# Button.net
KiCad netlist of a schematic drawn in EAGLE
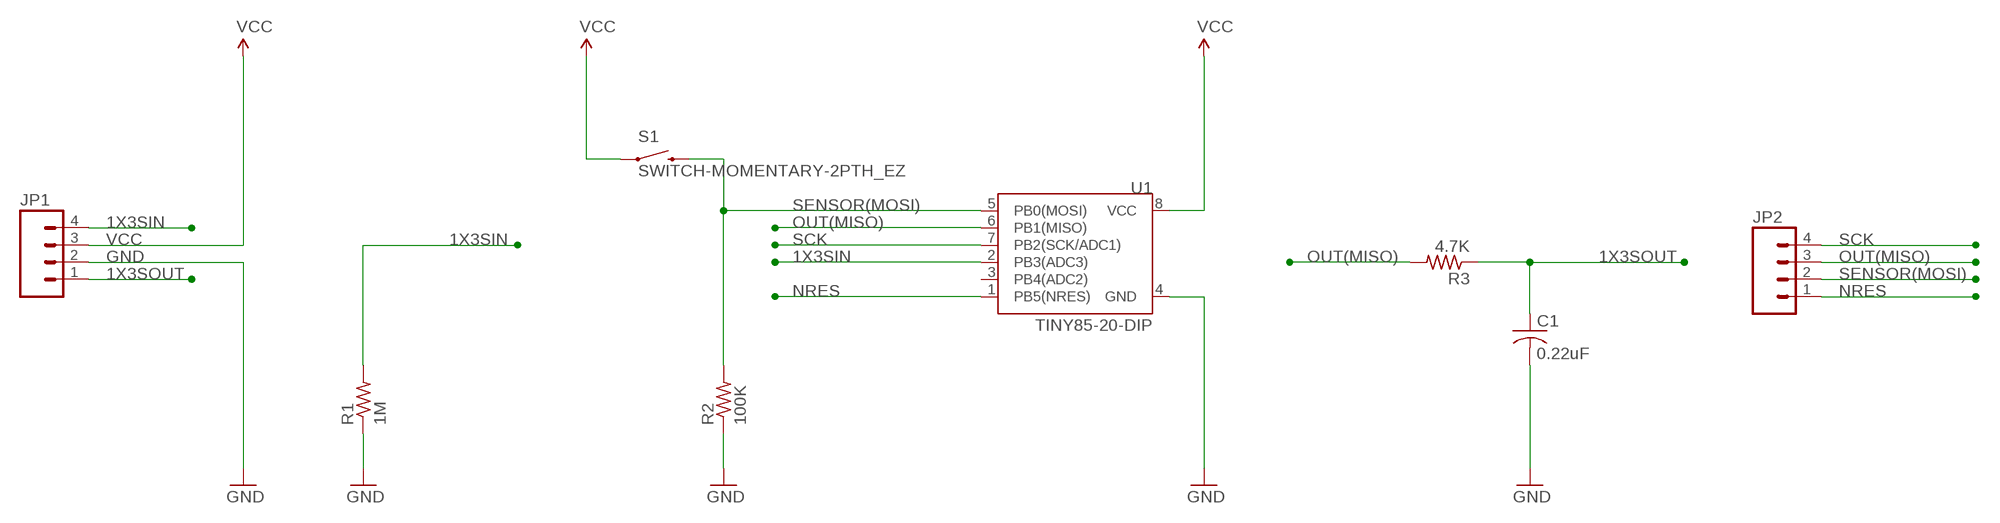
[diagram p0: schematic, sheet 1]

(export (version "E")
  (design (tool "Eeschema 10.0.6"))
  (components
    (comp (ref "C1")
      (value "0.22uF")
      (footprint "eagle-import:C0402")
      (libsource (lib "eagle-import") (part "C-USC0402"))
    )
    (comp (ref "JP1")
      (value "M04PTH")
      (footprint "eagle-import:1X04")
      (libsource (lib "eagle-import") (part "M04PTH"))
    )
    (comp (ref "JP2")
      (value "M04PTH")
      (footprint "eagle-import:1X04")
      (libsource (lib "eagle-import") (part "M04PTH"))
    )
    (comp (ref "R1")
      (value "1M")
      (footprint "eagle-import:R0603")
      (libsource (lib "eagle-import") (part "R-US_R0603"))
    )
    (comp (ref "R2")
      (value "100K")
      (footprint "eagle-import:R0603")
      (libsource (lib "eagle-import") (part "R-US_R0603"))
    )
    (comp (ref "R3")
      (value "4.7K")
      (footprint "eagle-import:R0603")
      (libsource (lib "eagle-import") (part "R-US_R0603"))
    )
    (comp (ref "S1")
      (value "SWITCH-MOMENTARY-2PTH_EZ")
      (footprint "eagle-import:TACTILE-PTH-EZ")
      (libsource (lib "eagle-import") (part "SWITCH-MOMENTARY-2PTH_EZ"))
    )
    (comp (ref "U1")
      (value "TINY85-20-DIP")
      (footprint "eagle-import:DIP08")
      (libsource (lib "eagle-import") (part "ATTINY45TINY85-20-DIP"))
    )
  )
  (nets
    (net (code "1") (name "/1X3SIN") (class "Default")
      (node (ref "JP1") (pin "4") (pinfunction "4_4") (pintype "passive"))
      (node (ref "R1") (pin "2") (pinfunction "2_2") (pintype "passive"))
      (node (ref "U1") (pin "2") (pinfunction "PB3(ADC3)_2") (pintype "bidirectional"))
    )
    (net (code "2") (name "/1X3SOUT") (class "Default")
      (node (ref "C1") (pin "1") (pinfunction "1_1") (pintype "passive"))
      (node (ref "JP1") (pin "1") (pinfunction "1_1") (pintype "passive"))
      (node (ref "R3") (pin "1") (pinfunction "1_1") (pintype "passive"))
    )
    (net (code "3") (name "/NRES") (class "Default")
      (node (ref "JP2") (pin "1") (pinfunction "1_1") (pintype "passive"))
      (node (ref "U1") (pin "1") (pinfunction "PB5(NRES)_1") (pintype "bidirectional"))
    )
    (net (code "4") (name "/OUT(MISO)") (class "Default")
      (node (ref "JP2") (pin "3") (pinfunction "3_3") (pintype "passive"))
      (node (ref "R3") (pin "2") (pinfunction "2_2") (pintype "passive"))
      (node (ref "U1") (pin "6") (pinfunction "PB1(MISO)_6") (pintype "bidirectional"))
    )
    (net (code "5") (name "/SCK") (class "Default")
      (node (ref "JP2") (pin "4") (pinfunction "4_4") (pintype "passive"))
      (node (ref "U1") (pin "7") (pinfunction "PB2(SCK/ADC1)_7") (pintype "bidirectional"))
    )
    (net (code "6") (name "/SENSOR(MOSI)") (class "Default")
      (node (ref "JP2") (pin "2") (pinfunction "2_2") (pintype "passive"))
      (node (ref "R2") (pin "2") (pinfunction "2_2") (pintype "passive"))
      (node (ref "S1") (pin "3") (pinfunction "2_3") (pintype "passive"))
      (node (ref "U1") (pin "5") (pinfunction "PB0(MOSI)_5") (pintype "bidirectional"))
    )
    (net (code "7") (name "GND") (class "Default")
      (node (ref "C1") (pin "2") (pinfunction "2_2") (pintype "passive"))
      (node (ref "JP1") (pin "2") (pinfunction "2_2") (pintype "passive"))
      (node (ref "R1") (pin "1") (pinfunction "1_1") (pintype "passive"))
      (node (ref "R2") (pin "1") (pinfunction "1_1") (pintype "passive"))
      (node (ref "U1") (pin "4") (pinfunction "GND_4") (pintype "bidirectional"))
    )
    (net (code "8") (name "VCC") (class "Default")
      (node (ref "JP1") (pin "3") (pinfunction "3_3") (pintype "passive"))
      (node (ref "S1") (pin "1") (pinfunction "1_1") (pintype "passive"))
      (node (ref "U1") (pin "8") (pinfunction "VCC_8") (pintype "bidirectional"))
    )
    (net (code "9") (name "unconnected-(U1-PB4(ADC2)-Pad3)") (class "Default")
      (node (ref "U1") (pin "3") (pinfunction "PB4(ADC2)_3") (pintype "bidirectional"))
    )
  )
)
